# CP2102_USB_To_UART.net
KiCad netlist of a schematic drawn in Altium Designer
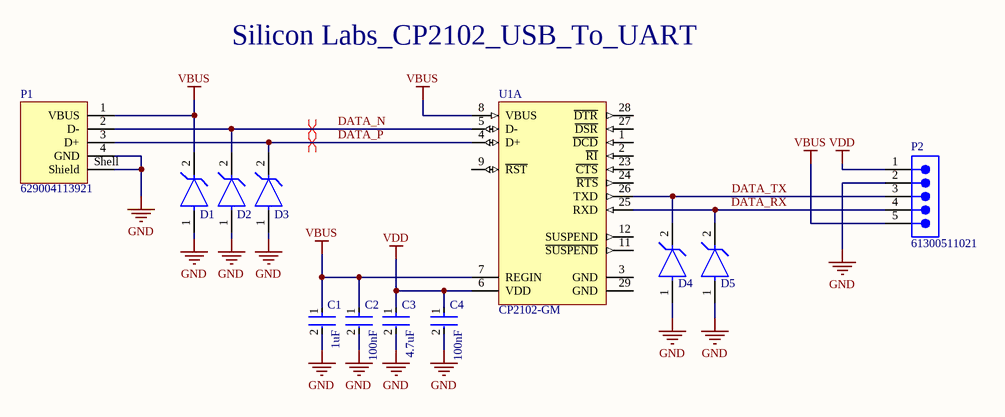
[diagram p0: CP2102_USB_To_UART.SchDoc]

(export (version "E")
  (design (tool "Eeschema 10.0.6"))
  (components
    (comp (ref "C1")
      (value "CC0402KRX5R6BB105")
      (footprint "FP-CC0402-MFG")
      (description "CAP CER 1UF 10V X5R 0402")
      (fields
        (field (name "OCTOPART") "https://octopart.com/cc0402krx5r6bb105-yageo-42244620")
        (field (name "TOLERANCE") "0.1")
        (field (name "CAPACITANCE") "1uF")
      )
      (libsource (lib "Altium Content Vault") (part "11868f565c42a9108669ba33697ecf6"))
    )
    (comp (ref "C2")
      (value "C1005X7R1C104K050BC")
      (footprint "FP-C1005-050-0_05-MFG")
      (description "Multilayer Ceramic Capacitors 100nF ±10% 16V X7R SMD 0402")
      (fields
        (field (name "VOLTAGE") "16V")
        (field (name "CAPACITANCE") "100nF")
        (field (name "TOLERANCE") "10%")
      )
      (libsource (lib "Altium Content Vault") (part "b4654b650e69147ec39a6b967a45e02"))
    )
    (comp (ref "C3")
      (value "GRM155R61A475MEAAD")
      (footprint "FP-GRM155-0_15-MFG")
      (description "Chip Multilayer Ceramic Capacitors for General Purpose, 0402, 4.7uF, X5R, 15%, 20%, 10V")
      (fields (field (name "CAPACITANCE") "4.7uF") (field (name "TOLERANCE") "20%"))
      (libsource (lib "Altium Content Vault") (part "b4654b650e69147ec39a6b967a45e02"))
    )
    (comp (ref "C4")
      (value "C1005X7R1C104K050BC")
      (footprint "FP-C1005-050-0_05-MFG")
      (description "Multilayer Ceramic Capacitors 100nF ±10% 16V X7R SMD 0402")
      (fields
        (field (name "VOLTAGE") "16V")
        (field (name "CAPACITANCE") "100nF")
        (field (name "TOLERANCE") "10%")
      )
      (libsource (lib "Altium Content Vault") (part "b4654b650e69147ec39a6b967a45e02"))
    )
    (comp (ref "D1")
      (value "UCLAMP3601P.TNT")
      (footprint "FP-SLP1006P2-MFG")
      (description "TVS DIODE 33VWM 60VC SLP1006P2")
      (libsource (lib "Altium Content Vault") (part "3fba79ac723ca0a4e69928609483429"))
    )
    (comp (ref "D2")
      (value "UCLAMP3601P.TNT")
      (footprint "FP-SLP1006P2-MFG")
      (description "TVS DIODE 33VWM 60VC SLP1006P2")
      (libsource (lib "Altium Content Vault") (part "3fba79ac723ca0a4e69928609483429"))
    )
    (comp (ref "D3")
      (value "UCLAMP3601P.TNT")
      (footprint "FP-SLP1006P2-MFG")
      (description "TVS DIODE 33VWM 60VC SLP1006P2")
      (libsource (lib "Altium Content Vault") (part "3fba79ac723ca0a4e69928609483429"))
    )
    (comp (ref "D4")
      (value "UCLAMP3601P.TNT")
      (footprint "FP-SLP1006P2-MFG")
      (description "TVS DIODE 33VWM 60VC SLP1006P2")
      (libsource (lib "Altium Content Vault") (part "3fba79ac723ca0a4e69928609483429"))
    )
    (comp (ref "D5")
      (value "UCLAMP3601P.TNT")
      (footprint "FP-SLP1006P2-MFG")
      (description "TVS DIODE 33VWM 60VC SLP1006P2")
      (libsource (lib "Altium Content Vault") (part "3fba79ac723ca0a4e69928609483429"))
    )
    (comp (ref "P1")
      (value "629004113921")
      (footprint "629004113921")
      (libsource (lib "Altium Content Vault") (part "USB 2.0_Type A_Plug_1 Port"))
    )
    (comp (ref "P2")
      (value "61300511021")
      (footprint "61300511021")
      (libsource (lib "Altium Content Vault") (part "Header_Male_1R_05P"))
    )
    (comp (ref "U1")
      (value "CP2102-GM")
      (footprint "SLAB-QFN-28-3125x3125TP_N")
      (description "Single-Chip USB to UART Bridge, 1024 Bytes EEPROM, -40 to 85 degC, 28-pin QFN, Tube")
      (fields (field (name "MANUFACTURER") "Silicon Labs"))
      (libsource (lib "Altium Content Vault") (part "SLAB-CP210X-QFN-28-29"))
    )
  )
  (nets
    (net (code "1") (name "/DATA_N") (class "Default")
      (node (ref "D2") (pin "2") (pinfunction "C_2") (pintype "passive"))
      (node (ref "P1") (pin "2") (pinfunction "D-_2") (pintype "passive"))
      (node (ref "U1") (pin "5") (pinfunction "D-_5") (pintype "bidirectional"))
    )
    (net (code "2") (name "/DATA_P") (class "Default")
      (node (ref "D3") (pin "2") (pinfunction "C_2") (pintype "passive"))
      (node (ref "P1") (pin "3") (pinfunction "D+_3") (pintype "passive"))
      (node (ref "U1") (pin "4") (pinfunction "D+_4") (pintype "bidirectional"))
    )
    (net (code "3") (name "/DATA_RX") (class "Default")
      (node (ref "D5") (pin "2") (pinfunction "C_2") (pintype "passive"))
      (node (ref "P2") (pin "4") (pinfunction "4_4") (pintype "passive"))
      (node (ref "U1") (pin "25") (pinfunction "RXD_25") (pintype "input"))
    )
    (net (code "4") (name "/DATA_TX") (class "Default")
      (node (ref "D4") (pin "2") (pinfunction "C_2") (pintype "passive"))
      (node (ref "P2") (pin "3") (pinfunction "3_3") (pintype "passive"))
      (node (ref "U1") (pin "26") (pinfunction "TXD_26") (pintype "output"))
    )
    (net (code "5") (name "GND") (class "Default")
      (node (ref "C1") (pin "2") (pinfunction "2_2") (pintype "passive"))
      (node (ref "C2") (pin "2") (pinfunction "2_2") (pintype "passive"))
      (node (ref "C3") (pin "2") (pinfunction "2_2") (pintype "passive"))
      (node (ref "C4") (pin "2") (pinfunction "2_2") (pintype "passive"))
      (node (ref "D1") (pin "1") (pinfunction "A_1") (pintype "passive"))
      (node (ref "D2") (pin "1") (pinfunction "A_1") (pintype "passive"))
      (node (ref "D3") (pin "1") (pinfunction "A_1") (pintype "passive"))
      (node (ref "D4") (pin "1") (pinfunction "A_1") (pintype "passive"))
      (node (ref "D5") (pin "1") (pinfunction "A_1") (pintype "passive"))
      (node (ref "P1") (pin "4") (pinfunction "GND_4") (pintype "passive"))
      (node (ref "P1") (pin "Shell") (pinfunction "Shield_Shell") (pintype "passive"))
      (node (ref "P2") (pin "2") (pinfunction "2_2") (pintype "passive"))
    )
    (net (code "6") (name "VBUS") (class "Default")
      (node (ref "C1") (pin "1") (pinfunction "1_1") (pintype "passive"))
      (node (ref "C2") (pin "1") (pinfunction "1_1") (pintype "passive"))
      (node (ref "D1") (pin "2") (pinfunction "C_2") (pintype "passive"))
      (node (ref "P1") (pin "1") (pinfunction "VBUS_1") (pintype "passive"))
      (node (ref "P2") (pin "5") (pinfunction "5_5") (pintype "passive"))
      (node (ref "U1") (pin "7") (pinfunction "REGIN_7") (pintype "power_in"))
      (node (ref "U1") (pin "8") (pinfunction "VBUS_8") (pintype "input"))
    )
    (net (code "7") (name "VDD") (class "Default")
      (node (ref "C3") (pin "1") (pinfunction "1_1") (pintype "passive"))
      (node (ref "C4") (pin "1") (pinfunction "1_1") (pintype "passive"))
      (node (ref "P2") (pin "1") (pinfunction "1_1") (pintype "passive"))
      (node (ref "U1") (pin "6") (pinfunction "VDD_6") (pintype "power_in"))
    )
    (net (code "8") (name "unconnected-(U1A-GND-Pad3)") (class "Default")
      (node (ref "U1") (pin "3") (pinfunction "GND_3") (pintype "power_in"))
    )
    (net (code "9") (name "unconnected-(U1A-GND-Pad29)") (class "Default")
      (node (ref "U1") (pin "29") (pinfunction "GND_29") (pintype "power_in"))
    )
    (net (code "10") (name "unconnected-(U1A-SUSPEND-Pad12)") (class "Default")
      (node (ref "U1") (pin "12") (pinfunction "SUSPEND_12") (pintype "output"))
    )
    (net (code "11") (name "unconnected-(U1A-~{CTS}-Pad23)") (class "Default")
      (node (ref "U1") (pin "23") (pinfunction "~{CTS}_23") (pintype "input"))
    )
    (net (code "12") (name "unconnected-(U1A-~{DCD}-Pad1)") (class "Default")
      (node (ref "U1") (pin "1") (pinfunction "~{DCD}_1") (pintype "input"))
    )
    (net (code "13") (name "unconnected-(U1A-~{DSR}-Pad27)") (class "Default")
      (node (ref "U1") (pin "27") (pinfunction "~{DSR}_27") (pintype "input"))
    )
    (net (code "14") (name "unconnected-(U1A-~{DTR}-Pad28)") (class "Default")
      (node (ref "U1") (pin "28") (pinfunction "~{DTR}_28") (pintype "output"))
    )
    (net (code "15") (name "unconnected-(U1A-~{RI}-Pad2)") (class "Default")
      (node (ref "U1") (pin "2") (pinfunction "~{RI}_2") (pintype "input"))
    )
    (net (code "16") (name "unconnected-(U1A-~{RST}-Pad9)") (class "Default")
      (node (ref "U1") (pin "9") (pinfunction "~{RST}_9") (pintype "bidirectional"))
    )
    (net (code "17") (name "unconnected-(U1A-~{RTS}-Pad24)") (class "Default")
      (node (ref "U1") (pin "24") (pinfunction "~{RTS}_24") (pintype "output"))
    )
    (net (code "18") (name "unconnected-(U1A-~{SUSPEND}-Pad11)") (class "Default")
      (node (ref "U1") (pin "11") (pinfunction "~{SUSPEND}_11") (pintype "output"))
    )
  )
)
